# MatrixPi.net
KiCad netlist of a schematic drawn in EAGLE
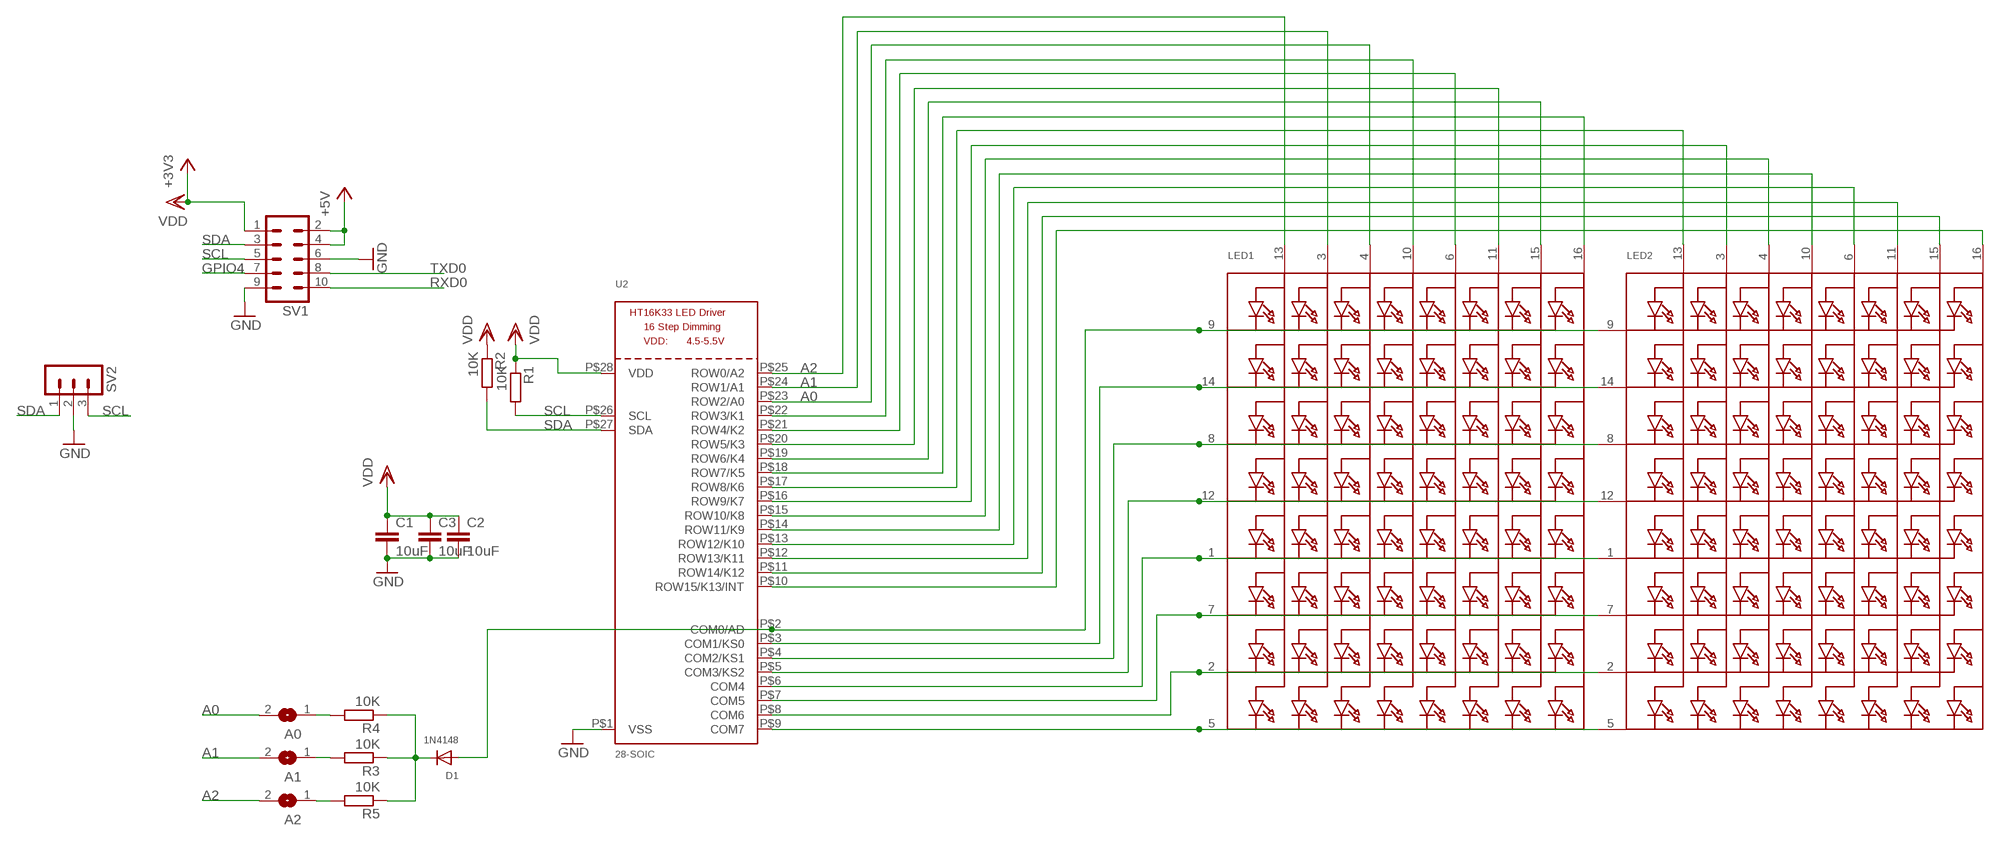
[diagram p0: schematic, sheet 1]

(export (version "E")
  (design (tool "Eeschema 10.0.6"))
  (components
    (comp (ref "A0")
      (value "SOLDERJUMPERREFLOW_NOPASTE")
      (footprint "eagle-import:SOLDERJUMPER_REFLOW_NOPASTE")
      (libsource (lib "eagle-import") (part "SOLDERJUMPERREFLOW_NOPASTE"))
    )
    (comp (ref "A1")
      (value "SOLDERJUMPERREFLOW_NOPASTE")
      (footprint "eagle-import:SOLDERJUMPER_REFLOW_NOPASTE")
      (libsource (lib "eagle-import") (part "SOLDERJUMPERREFLOW_NOPASTE"))
    )
    (comp (ref "A2")
      (value "SOLDERJUMPERREFLOW_NOPASTE")
      (footprint "eagle-import:SOLDERJUMPER_REFLOW_NOPASTE")
      (libsource (lib "eagle-import") (part "SOLDERJUMPERREFLOW_NOPASTE"))
    )
    (comp (ref "C1")
      (value "10uF")
      (footprint "eagle-import:C0805")
      (libsource (lib "eagle-import") (part "C-EUC0805"))
    )
    (comp (ref "C2")
      (value "10uF")
      (footprint "eagle-import:C0805")
      (libsource (lib "eagle-import") (part "C-EUC0805"))
    )
    (comp (ref "C3")
      (value "10uF")
      (footprint "eagle-import:C0805")
      (libsource (lib "eagle-import") (part "C-EUC0805"))
    )
    (comp (ref "D1")
      (value "1N4148")
      (footprint "eagle-import:SOD-323F")
      (libsource (lib "eagle-import") (part "DIODESOD-323F"))
    )
    (comp (ref "LED1")
      (value "MATRIX_8X8_ROWCATHODE")
      (footprint "eagle-import:TA15-11CGKWA")
      (libsource (lib "eagle-import") (part "MATRIX_8X8_ROWCATHODE"))
    )
    (comp (ref "LED2")
      (value "MATRIX_8X8_ROWCATHODE")
      (footprint "eagle-import:TA15-11CGKWA")
      (libsource (lib "eagle-import") (part "MATRIX_8X8_ROWCATHODE"))
    )
    (comp (ref "R1")
      (value "10K")
      (footprint "eagle-import:M0805")
      (libsource (lib "eagle-import") (part "R-EU_M0805"))
    )
    (comp (ref "R2")
      (value "10K")
      (footprint "eagle-import:M0805")
      (libsource (lib "eagle-import") (part "R-EU_M0805"))
    )
    (comp (ref "R3")
      (value "10K")
      (footprint "eagle-import:M0805")
      (libsource (lib "eagle-import") (part "R-EU_M0805"))
    )
    (comp (ref "R4")
      (value "10K")
      (footprint "eagle-import:M0805")
      (libsource (lib "eagle-import") (part "R-EU_M0805"))
    )
    (comp (ref "R5")
      (value "10K")
      (footprint "eagle-import:M0805")
      (libsource (lib "eagle-import") (part "R-EU_M0805"))
    )
    (comp (ref "SV1")
      (value "MA05-2")
      (footprint "eagle-import:MA05-2")
      (libsource (lib "eagle-import") (part "MA05-2"))
    )
    (comp (ref "SV2")
      (value "MA03-1")
      (footprint "eagle-import:MA03-1")
      (libsource (lib "eagle-import") (part "MA03-1"))
    )
    (comp (ref "U2")
      (value "28-SOIC")
      (footprint "eagle-import:SOP28_300MIL")
      (libsource (lib "eagle-import") (part "HT16K33_SOP28"))
    )
  )
  (nets
    (net (code "1") (name "+3V3") (class "Default")
      (node (ref "C1") (pin "1") (pinfunction "1_1") (pintype "passive"))
      (node (ref "C2") (pin "1") (pinfunction "1_1") (pintype "passive"))
      (node (ref "C3") (pin "1") (pinfunction "1_1") (pintype "passive"))
      (node (ref "R1") (pin "1") (pinfunction "1_1") (pintype "passive"))
      (node (ref "R2") (pin "1") (pinfunction "1_1") (pintype "passive"))
      (node (ref "SV1") (pin "1") (pinfunction "1_1") (pintype "passive"))
      (node (ref "U2") (pin "P$28") (pinfunction "VDD_P$28") (pintype "bidirectional"))
    )
    (net (code "2") (name "+5V") (class "Default")
      (node (ref "SV1") (pin "2") (pinfunction "2_2") (pintype "passive"))
      (node (ref "SV1") (pin "4") (pinfunction "4_4") (pintype "passive"))
    )
    (net (code "3") (name "/A0") (class "Default")
      (node (ref "A0") (pin "2") (pinfunction "2_2") (pintype "passive"))
      (node (ref "LED1") (pin "4") (pinfunction "A3_4") (pintype "bidirectional"))
      (node (ref "U2") (pin "P$23") (pinfunction "ROW2/A0_P$23") (pintype "bidirectional"))
    )
    (net (code "4") (name "/A1") (class "Default")
      (node (ref "A1") (pin "2") (pinfunction "2_2") (pintype "passive"))
      (node (ref "LED1") (pin "3") (pinfunction "A2_3") (pintype "bidirectional"))
      (node (ref "U2") (pin "P$24") (pinfunction "ROW1/A1_P$24") (pintype "bidirectional"))
    )
    (net (code "5") (name "/A2") (class "Default")
      (node (ref "A2") (pin "2") (pinfunction "2_2") (pintype "passive"))
      (node (ref "LED1") (pin "13") (pinfunction "A1_13") (pintype "bidirectional"))
      (node (ref "U2") (pin "P$25") (pinfunction "ROW0/A2_P$25") (pintype "bidirectional"))
    )
    (net (code "6") (name "/GPIO4") (class "Default")
      (node (ref "SV1") (pin "7") (pinfunction "7_7") (pintype "passive"))
    )
    (net (code "7") (name "/RXD0") (class "Default")
      (node (ref "SV1") (pin "10") (pinfunction "10_10") (pintype "passive"))
    )
    (net (code "8") (name "/SCL") (class "Default")
      (node (ref "R1") (pin "2") (pinfunction "2_2") (pintype "passive"))
      (node (ref "SV1") (pin "5") (pinfunction "5_5") (pintype "passive"))
      (node (ref "SV2") (pin "3") (pinfunction "3_3") (pintype "passive"))
      (node (ref "U2") (pin "P$26") (pinfunction "SCL_P$26") (pintype "bidirectional"))
    )
    (net (code "9") (name "/SDA") (class "Default")
      (node (ref "R2") (pin "2") (pinfunction "2_2") (pintype "passive"))
      (node (ref "SV1") (pin "3") (pinfunction "3_3") (pintype "passive"))
      (node (ref "SV2") (pin "1") (pinfunction "1_1") (pintype "passive"))
      (node (ref "U2") (pin "P$27") (pinfunction "SDA_P$27") (pintype "bidirectional"))
    )
    (net (code "10") (name "/TXD0") (class "Default")
      (node (ref "SV1") (pin "8") (pinfunction "8_8") (pintype "passive"))
    )
    (net (code "11") (name "GND") (class "Default")
      (node (ref "C1") (pin "2") (pinfunction "2_2") (pintype "passive"))
      (node (ref "C2") (pin "2") (pinfunction "2_2") (pintype "passive"))
      (node (ref "C3") (pin "2") (pinfunction "2_2") (pintype "passive"))
      (node (ref "SV1") (pin "6") (pinfunction "6_6") (pintype "passive"))
      (node (ref "SV1") (pin "9") (pinfunction "9_9") (pintype "passive"))
      (node (ref "SV2") (pin "2") (pinfunction "2_2") (pintype "passive"))
      (node (ref "U2") (pin "P$1") (pinfunction "VSS_P$1") (pintype "bidirectional"))
    )
    (net (code "12") (name "Net-(A0-Pad1)") (class "Default")
      (node (ref "A0") (pin "1") (pinfunction "1_1") (pintype "passive"))
      (node (ref "R4") (pin "2") (pinfunction "2_2") (pintype "passive"))
    )
    (net (code "13") (name "Net-(A1-Pad1)") (class "Default")
      (node (ref "A1") (pin "1") (pinfunction "1_1") (pintype "passive"))
      (node (ref "R3") (pin "2") (pinfunction "2_2") (pintype "passive"))
    )
    (net (code "14") (name "Net-(A2-Pad1)") (class "Default")
      (node (ref "A2") (pin "1") (pinfunction "1_1") (pintype "passive"))
      (node (ref "R5") (pin "2") (pinfunction "2_2") (pintype "passive"))
    )
    (net (code "15") (name "Net-(D1-PadC)") (class "Default")
      (node (ref "D1") (pin "C") (pinfunction "C_C") (pintype "passive"))
      (node (ref "R3") (pin "1") (pinfunction "1_1") (pintype "passive"))
      (node (ref "R4") (pin "1") (pinfunction "1_1") (pintype "passive"))
      (node (ref "R5") (pin "1") (pinfunction "1_1") (pintype "passive"))
    )
    (net (code "16") (name "Net-(LED1-A4)") (class "Default")
      (node (ref "LED1") (pin "10") (pinfunction "A4_10") (pintype "bidirectional"))
      (node (ref "U2") (pin "P$22") (pinfunction "ROW3/K1_P$22") (pintype "bidirectional"))
    )
    (net (code "17") (name "Net-(LED1-A5)") (class "Default")
      (node (ref "LED1") (pin "6") (pinfunction "A5_6") (pintype "bidirectional"))
      (node (ref "U2") (pin "P$21") (pinfunction "ROW4/K2_P$21") (pintype "bidirectional"))
    )
    (net (code "18") (name "Net-(LED1-A6)") (class "Default")
      (node (ref "LED1") (pin "11") (pinfunction "A6_11") (pintype "bidirectional"))
      (node (ref "U2") (pin "P$20") (pinfunction "ROW5/K3_P$20") (pintype "bidirectional"))
    )
    (net (code "19") (name "Net-(LED1-A7)") (class "Default")
      (node (ref "LED1") (pin "15") (pinfunction "A7_15") (pintype "bidirectional"))
      (node (ref "U2") (pin "P$19") (pinfunction "ROW6/K4_P$19") (pintype "bidirectional"))
    )
    (net (code "20") (name "Net-(LED1-A8)") (class "Default")
      (node (ref "LED1") (pin "16") (pinfunction "A8_16") (pintype "bidirectional"))
      (node (ref "U2") (pin "P$18") (pinfunction "ROW7/K5_P$18") (pintype "bidirectional"))
    )
    (net (code "21") (name "Net-(LED1-K1)") (class "Default")
      (node (ref "D1") (pin "A") (pinfunction "A_A") (pintype "passive"))
      (node (ref "LED1") (pin "9") (pinfunction "K1_9") (pintype "bidirectional"))
      (node (ref "LED2") (pin "9") (pinfunction "K1_9") (pintype "bidirectional"))
      (node (ref "U2") (pin "P$2") (pinfunction "COM0/AD_P$2") (pintype "bidirectional"))
    )
    (net (code "22") (name "Net-(LED1-K2)") (class "Default")
      (node (ref "LED1") (pin "14") (pinfunction "K2_14") (pintype "bidirectional"))
      (node (ref "LED2") (pin "14") (pinfunction "K2_14") (pintype "bidirectional"))
      (node (ref "U2") (pin "P$3") (pinfunction "COM1/KS0_P$3") (pintype "bidirectional"))
    )
    (net (code "23") (name "Net-(LED1-K3)") (class "Default")
      (node (ref "LED1") (pin "8") (pinfunction "K3_8") (pintype "bidirectional"))
      (node (ref "LED2") (pin "8") (pinfunction "K3_8") (pintype "bidirectional"))
      (node (ref "U2") (pin "P$4") (pinfunction "COM2/KS1_P$4") (pintype "bidirectional"))
    )
    (net (code "24") (name "Net-(LED1-K4)") (class "Default")
      (node (ref "LED1") (pin "12") (pinfunction "K4_12") (pintype "bidirectional"))
      (node (ref "LED2") (pin "12") (pinfunction "K4_12") (pintype "bidirectional"))
      (node (ref "U2") (pin "P$5") (pinfunction "COM3/KS2_P$5") (pintype "bidirectional"))
    )
    (net (code "25") (name "Net-(LED1-K5)") (class "Default")
      (node (ref "LED1") (pin "1") (pinfunction "K5_1") (pintype "bidirectional"))
      (node (ref "LED2") (pin "1") (pinfunction "K5_1") (pintype "bidirectional"))
      (node (ref "U2") (pin "P$6") (pinfunction "COM4_P$6") (pintype "bidirectional"))
    )
    (net (code "26") (name "Net-(LED1-K6)") (class "Default")
      (node (ref "LED1") (pin "7") (pinfunction "K6_7") (pintype "bidirectional"))
      (node (ref "LED2") (pin "7") (pinfunction "K6_7") (pintype "bidirectional"))
      (node (ref "U2") (pin "P$7") (pinfunction "COM5_P$7") (pintype "bidirectional"))
    )
    (net (code "27") (name "Net-(LED1-K7)") (class "Default")
      (node (ref "LED1") (pin "2") (pinfunction "K7_2") (pintype "bidirectional"))
      (node (ref "LED2") (pin "2") (pinfunction "K7_2") (pintype "bidirectional"))
      (node (ref "U2") (pin "P$8") (pinfunction "COM6_P$8") (pintype "bidirectional"))
    )
    (net (code "28") (name "Net-(LED1-K8)") (class "Default")
      (node (ref "LED1") (pin "5") (pinfunction "K8_5") (pintype "bidirectional"))
      (node (ref "LED2") (pin "5") (pinfunction "K8_5") (pintype "bidirectional"))
      (node (ref "U2") (pin "P$9") (pinfunction "COM7_P$9") (pintype "bidirectional"))
    )
    (net (code "29") (name "Net-(LED2-A1)") (class "Default")
      (node (ref "LED2") (pin "13") (pinfunction "A1_13") (pintype "bidirectional"))
      (node (ref "U2") (pin "P$17") (pinfunction "ROW8/K6_P$17") (pintype "bidirectional"))
    )
    (net (code "30") (name "Net-(LED2-A2)") (class "Default")
      (node (ref "LED2") (pin "3") (pinfunction "A2_3") (pintype "bidirectional"))
      (node (ref "U2") (pin "P$16") (pinfunction "ROW9/K7_P$16") (pintype "bidirectional"))
    )
    (net (code "31") (name "Net-(LED2-A3)") (class "Default")
      (node (ref "LED2") (pin "4") (pinfunction "A3_4") (pintype "bidirectional"))
      (node (ref "U2") (pin "P$15") (pinfunction "ROW10/K8_P$15") (pintype "bidirectional"))
    )
    (net (code "32") (name "Net-(LED2-A4)") (class "Default")
      (node (ref "LED2") (pin "10") (pinfunction "A4_10") (pintype "bidirectional"))
      (node (ref "U2") (pin "P$14") (pinfunction "ROW11/K9_P$14") (pintype "bidirectional"))
    )
    (net (code "33") (name "Net-(LED2-A5)") (class "Default")
      (node (ref "LED2") (pin "6") (pinfunction "A5_6") (pintype "bidirectional"))
      (node (ref "U2") (pin "P$13") (pinfunction "ROW12/K10_P$13") (pintype "bidirectional"))
    )
    (net (code "34") (name "Net-(LED2-A6)") (class "Default")
      (node (ref "LED2") (pin "11") (pinfunction "A6_11") (pintype "bidirectional"))
      (node (ref "U2") (pin "P$12") (pinfunction "ROW13/K11_P$12") (pintype "bidirectional"))
    )
    (net (code "35") (name "Net-(LED2-A7)") (class "Default")
      (node (ref "LED2") (pin "15") (pinfunction "A7_15") (pintype "bidirectional"))
      (node (ref "U2") (pin "P$11") (pinfunction "ROW14/K12_P$11") (pintype "bidirectional"))
    )
    (net (code "36") (name "Net-(LED2-A8)") (class "Default")
      (node (ref "LED2") (pin "16") (pinfunction "A8_16") (pintype "bidirectional"))
      (node (ref "U2") (pin "P$10") (pinfunction "ROW15/K13/INT_P$10") (pintype "bidirectional"))
    )
  )
)
